# uC_assembly.net
KiCad netlist of a schematic drawn in Altium Designer
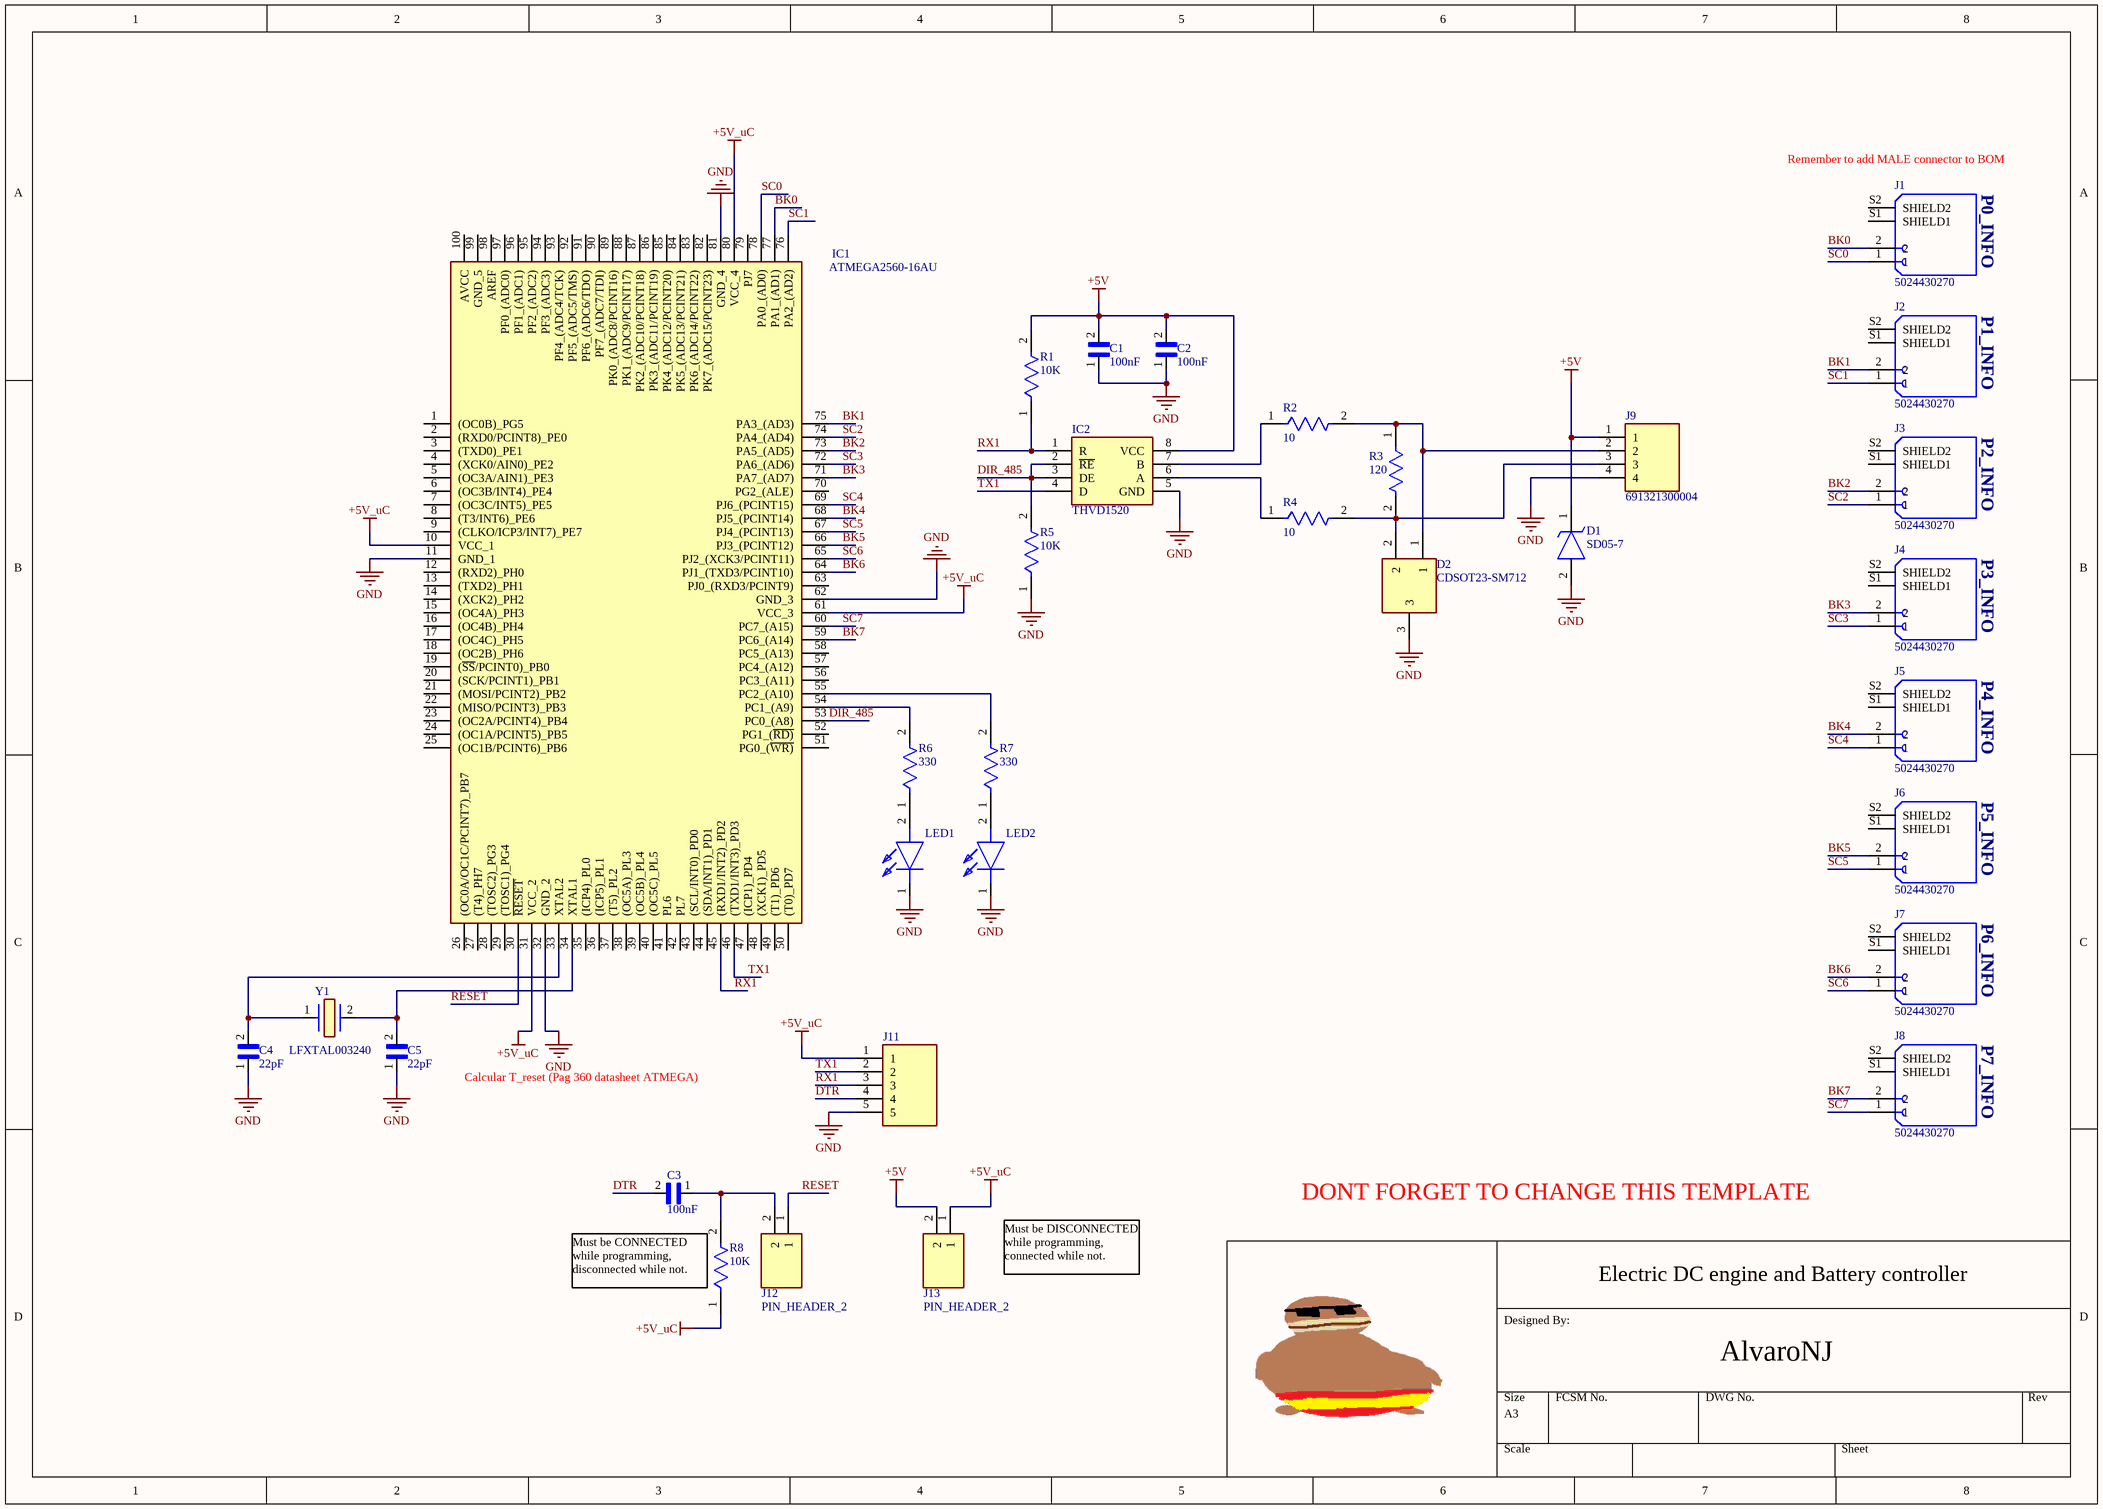
[diagram p0: uC_assembly.SchDoc]

(export (version "E")
  (design (tool "Eeschema 10.0.6"))
  (components
    (comp (ref "C1")
      (value "100nF")
      (footprint "0603C")
      (description "Cap Ceramic 22pF")
      (fields
        (field (name "MANUFACTURER") "Kyocera")
        (field (name "MANUFACTURER PART NUMBER") "KGM15BR71E104KT")
      )
      (libsource (lib "") (part "Ceramic_Capacitor_1"))
    )
    (comp (ref "C2")
      (value "100nF")
      (footprint "0603C")
      (description "Cap Ceramic 22pF")
      (fields
        (field (name "MANUFACTURER") "Kyocera")
        (field (name "MANUFACTURER PART NUMBER") "KGM15BR71E104KT")
      )
      (libsource (lib "") (part "Ceramic_Capacitor_1"))
    )
    (comp (ref "C3")
      (value "100nF")
      (footprint "0603C")
      (description "Cap Ceramic 22pF")
      (fields
        (field (name "MANUFACTURER") "Kyocera")
        (field (name "MANUFACTURER PART NUMBER") "KGM15BR71E104KT")
      )
      (libsource (lib "Schlib1") (part "Ceramic_Capacitor"))
    )
    (comp (ref "C4")
      (value "22pF")
      (footprint "0603C")
      (description "Cap Ceramic 22pF")
      (fields
        (field (name "MANUFACTURER") "Kyocera")
        (field (name "MANUFACTURER PART NUMBER") "KGM15ACG1C220KT")
      )
      (libsource (lib "") (part "Ceramic_Capacitor_1"))
    )
    (comp (ref "C5")
      (value "22pF")
      (footprint "0603C")
      (description "Cap Ceramic 22pF")
      (fields
        (field (name "MANUFACTURER") "Kyocera")
        (field (name "MANUFACTURER PART NUMBER") "KGM15ACG1C220KT")
      )
      (libsource (lib "") (part "Ceramic_Capacitor_1"))
    )
    (comp (ref "D1")
      (value "SD05-7")
      (footprint "PcbLib1:SOD2513X120N")
      (description "TVS Diode (Uni-directional)")
      (fields (field (name "MOUSER PART NUMBER") "621-SD05-7"))
      (libsource (lib "*") (part "SD05-7"))
    )
    (comp (ref "D2")
      (value "CDSOT23-SM712")
      (footprint "PcbLib1:SOT95P230X117-3N")
      (description "Diode")
      (fields (field (name "MOUSER PART NUMBER") "652-CDSOT23-SM712"))
      (libsource (lib "*") (part "CDSOT23-SM712"))
    )
    (comp (ref "IC1")
      (value "ATMEGA2560-16AU")
      (footprint "PcbLib1:QFP50P1600X1600X120-100N")
      (description "Integrated Circuit")
      (fields (field (name "MOUSER PART NUMBER") "556-ATMEGA2560-16AU"))
      (libsource (lib "Schlib1") (part "ATMEGA2560-16AU"))
    )
    (comp (ref "IC2")
      (value "THVD1520")
      (footprint "PcbLib1:SOIC127P600X175-8N")
      (description "Integrated Circuit")
      (libsource (lib "*") (part "THVD1520"))
    )
    (comp (ref "J1")
      (value "5024430270")
      (footprint "MOLEX_5024430270")
      (libsource (lib "Schlib1") (part "5024430270"))
    )
    (comp (ref "J2")
      (value "5024430270")
      (footprint "MOLEX_5024430270")
      (libsource (lib "Schlib1") (part "5024430270"))
    )
    (comp (ref "J3")
      (value "5024430270")
      (footprint "MOLEX_5024430270")
      (libsource (lib "Schlib1") (part "5024430270"))
    )
    (comp (ref "J4")
      (value "5024430270")
      (footprint "MOLEX_5024430270")
      (libsource (lib "Schlib1") (part "5024430270"))
    )
    (comp (ref "J5")
      (value "5024430270")
      (footprint "MOLEX_5024430270")
      (libsource (lib "Schlib1") (part "5024430270"))
    )
    (comp (ref "J6")
      (value "5024430270")
      (footprint "MOLEX_5024430270")
      (libsource (lib "Schlib1") (part "5024430270"))
    )
    (comp (ref "J7")
      (value "5024430270")
      (footprint "MOLEX_5024430270")
      (libsource (lib "Schlib1") (part "5024430270"))
    )
    (comp (ref "J8")
      (value "5024430270")
      (footprint "MOLEX_5024430270")
      (libsource (lib "Schlib1") (part "5024430270"))
    )
    (comp (ref "J9")
      (value "691321300004")
      (footprint "PcbLib1:SHDR4W80P0X381_1X4_1643X720X920P")
      (description "Connector")
      (fields (field (name "MOUSER PART NUMBER") "710-691321300004"))
      (libsource (lib "*") (part "691321300004"))
    )
    (comp (ref "J11")
      (value "MOLEX,_C-GRID_III,_90120,_8_WAY,_1_ROW,_STRAIGHT_PIN_HEADER")
      (footprint "HDRV8W65P0X254_1X8_2010X249X945P - duplicate")
      (description "Connector")
      (fields (field (name "MANUFACTURER_PART_NUMBER") "MOLEX"))
      (libsource (lib "Schlib1") (part "MOLEX,_C-GRID_III,_90120,_8_WAY,_1_ROW,_STRAIGHT_PIN_HEADER"))
    )
    (comp (ref "J12")
      (value "PIN_HEADER_2")
      (footprint "PINHEADER2")
      (description "Connector")
      (fields (field (name "MANUFACTURER_PART_NUMBER") "MOLEX"))
      (libsource (lib "Schlib1") (part "PIN_HEADER_2"))
    )
    (comp (ref "J13")
      (value "PIN_HEADER_2")
      (footprint "PINHEADER2")
      (description "Connector")
      (fields (field (name "MANUFACTURER_PART_NUMBER") "MOLEX"))
      (libsource (lib "Schlib1") (part "PIN_HEADER_2"))
    )
    (comp (ref "LED1")
      (value "LTST-C191KFKT")
      (footprint "PcbLib1:LEDC1608X55N")
      (description "LED")
      (fields (field (name "MANUFACTURER") "Lite-On"))
      (libsource (lib "*") (part "LTST-C191KFKT"))
    )
    (comp (ref "LED2")
      (value "LTST-C191KFKT")
      (footprint "PcbLib1:LEDC1608X55N")
      (description "LED")
      (fields
        (field (name "MANUFACTURER") "Lite-On")
        (field (name "MANUFACTURER PART NUMBER") "LTST-C191KGKT")
      )
      (libsource (lib "*") (part "LTST-C191KFKT"))
    )
    (comp (ref "R1")
      (value "10K")
      (footprint "0603R")
      (fields
        (field (name "MANUFACTURER") "Yageo")
        (field (name "MANUFACTURER PART NUMBER") "RC0603FR-1010KL")
      )
      (libsource (lib "Schlib1") (part "Resistor"))
    )
    (comp (ref "R2")
      (value "10")
      (footprint "0603R")
      (fields
        (field (name "MANUFACTURER") "Yageo")
        (field (name "MANUFACTURER PART NUMBER") "RC0603FR-0710RL")
      )
      (libsource (lib "Schlib1") (part "Resistor"))
    )
    (comp (ref "R3")
      (value "120")
      (footprint "1206R")
      (fields
        (field (name "MANUFACTURER") "Yageo")
        (field (name "MANUFACTURER PART NUMBER") "RC1206FR-07120RL")
      )
      (libsource (lib "Schlib1") (part "Resistor"))
    )
    (comp (ref "R4")
      (value "10")
      (footprint "0603R")
      (fields
        (field (name "MANUFACTURER") "Yageo")
        (field (name "MANUFACTURER PART NUMBER") "RC0603FR-0710RL")
      )
      (libsource (lib "Schlib1") (part "Resistor"))
    )
    (comp (ref "R5")
      (value "10K")
      (footprint "0603R")
      (fields
        (field (name "MANUFACTURER") "Yageo")
        (field (name "MANUFACTURER PART NUMBER") "RC0603FR-1010KL")
      )
      (libsource (lib "Schlib1") (part "Resistor"))
    )
    (comp (ref "R6")
      (value "330")
      (footprint "0603R")
      (fields
        (field (name "MANUFACTURER") "Yageo")
        (field (name "MANUFACTURER PART NUMBER") "RC0603FR-10330RL")
      )
      (libsource (lib "Schlib1") (part "Resistor"))
    )
    (comp (ref "R7")
      (value "330")
      (footprint "0603R")
      (fields
        (field (name "MANUFACTURER") "Yageo")
        (field (name "MANUFACTURER PART NUMBER") "RC0603FR-10330RL")
      )
      (libsource (lib "Schlib1") (part "Resistor"))
    )
    (comp (ref "R8")
      (value "10K")
      (footprint "0603R")
      (fields
        (field (name "MANUFACTURER") "Yageo")
        (field (name "MANUFACTURER PART NUMBER") "RC0603FR-1010KL")
      )
      (libsource (lib "Schlib1") (part "Resistor"))
    )
    (comp (ref "Y1")
      (value "LFXTAL003240")
      (footprint "IQD-HC-49-4H")
      (description "Crystal or Oscillator")
      (libsource (lib "Schlib1") (part "LFXTAL003240"))
    )
  )
  (nets
    (net (code "1") (name "+5V") (class "Default")
      (node (ref "C1") (pin "2") (pinfunction "2_2") (pintype "passive"))
      (node (ref "C2") (pin "2") (pinfunction "2_2") (pintype "passive"))
      (node (ref "D1") (pin "1") (pinfunction "K_1") (pintype "passive"))
      (node (ref "IC2") (pin "8") (pinfunction "VCC_8") (pintype "passive"))
      (node (ref "J13") (pin "2") (pinfunction "2_2") (pintype "passive"))
      (node (ref "J9") (pin "1") (pinfunction "1_1") (pintype "passive"))
      (node (ref "R1") (pin "2") (pinfunction "2_2") (pintype "passive"))
    )
    (net (code "2") (name "+5V_uC") (class "Default")
      (node (ref "IC1") (pin "10") (pinfunction "VCC_1_10") (pintype "passive"))
      (node (ref "IC1") (pin "31") (pinfunction "VCC_2_31") (pintype "passive"))
      (node (ref "IC1") (pin "61") (pinfunction "VCC_3_61") (pintype "passive"))
      (node (ref "IC1") (pin "80") (pinfunction "VCC_4_80") (pintype "passive"))
      (node (ref "J11") (pin "1") (pinfunction "1_1") (pintype "passive"))
      (node (ref "J13") (pin "1") (pinfunction "1_1") (pintype "passive"))
      (node (ref "R8") (pin "1") (pinfunction "1_1") (pintype "passive"))
    )
    (net (code "3") (name "/BK0") (class "Default")
      (node (ref "IC1") (pin "77") (pinfunction "PA1_(AD1)_77") (pintype "passive"))
      (node (ref "J1") (pin "2") (pinfunction "2_2") (pintype "passive"))
    )
    (net (code "4") (name "/BK1") (class "Default")
      (node (ref "IC1") (pin "75") (pinfunction "PA3_(AD3)_75") (pintype "passive"))
      (node (ref "J2") (pin "2") (pinfunction "2_2") (pintype "passive"))
    )
    (net (code "5") (name "/BK2") (class "Default")
      (node (ref "IC1") (pin "73") (pinfunction "PA5_(AD5)_73") (pintype "passive"))
      (node (ref "J3") (pin "2") (pinfunction "2_2") (pintype "passive"))
    )
    (net (code "6") (name "/BK3") (class "Default")
      (node (ref "IC1") (pin "71") (pinfunction "PA7_(AD7)_71") (pintype "passive"))
      (node (ref "J4") (pin "2") (pinfunction "2_2") (pintype "passive"))
    )
    (net (code "7") (name "/BK4") (class "Default")
      (node (ref "IC1") (pin "68") (pinfunction "PJ5_(PCINT14)_68") (pintype "passive"))
      (node (ref "J5") (pin "2") (pinfunction "2_2") (pintype "passive"))
    )
    (net (code "8") (name "/BK5") (class "Default")
      (node (ref "IC1") (pin "66") (pinfunction "PJ3_(PCINT12)_66") (pintype "passive"))
      (node (ref "J6") (pin "2") (pinfunction "2_2") (pintype "passive"))
    )
    (net (code "9") (name "/BK6") (class "Default")
      (node (ref "IC1") (pin "64") (pinfunction "PJ1_(TXD3/PCINT10)_64") (pintype "passive"))
      (node (ref "J7") (pin "2") (pinfunction "2_2") (pintype "passive"))
    )
    (net (code "10") (name "/BK7") (class "Default")
      (node (ref "IC1") (pin "59") (pinfunction "PC6_(A14)_59") (pintype "passive"))
      (node (ref "J8") (pin "2") (pinfunction "2_2") (pintype "passive"))
    )
    (net (code "11") (name "/DIR_485") (class "Default")
      (node (ref "IC1") (pin "53") (pinfunction "PC0_(A8)_53") (pintype "passive"))
      (node (ref "IC2") (pin "2") (pinfunction "~{RE}_2") (pintype "passive"))
      (node (ref "IC2") (pin "3") (pinfunction "DE_3") (pintype "passive"))
      (node (ref "R5") (pin "2") (pinfunction "2_2") (pintype "passive"))
    )
    (net (code "12") (name "/DTR") (class "Default")
      (node (ref "C3") (pin "2") (pinfunction "2_2") (pintype "passive"))
      (node (ref "J11") (pin "4") (pinfunction "4_4") (pintype "passive"))
    )
    (net (code "13") (name "/RESET") (class "Default")
      (node (ref "IC1") (pin "30") (pinfunction "~{RESET}_30") (pintype "passive"))
      (node (ref "J12") (pin "1") (pinfunction "1_1") (pintype "passive"))
    )
    (net (code "14") (name "/RX1") (class "Default")
      (node (ref "IC1") (pin "45") (pinfunction "(RXD1/INT2)_PD2_45") (pintype "passive"))
      (node (ref "IC2") (pin "1") (pinfunction "R_1") (pintype "passive"))
      (node (ref "J11") (pin "3") (pinfunction "3_3") (pintype "passive"))
      (node (ref "R1") (pin "1") (pinfunction "1_1") (pintype "passive"))
    )
    (net (code "15") (name "/SC0") (class "Default")
      (node (ref "IC1") (pin "78") (pinfunction "PA0_(AD0)_78") (pintype "passive"))
      (node (ref "J1") (pin "1") (pinfunction "1_1") (pintype "passive"))
    )
    (net (code "16") (name "/SC1") (class "Default")
      (node (ref "IC1") (pin "76") (pinfunction "PA2_(AD2)_76") (pintype "passive"))
      (node (ref "J2") (pin "1") (pinfunction "1_1") (pintype "passive"))
    )
    (net (code "17") (name "/SC2") (class "Default")
      (node (ref "IC1") (pin "74") (pinfunction "PA4_(AD4)_74") (pintype "passive"))
      (node (ref "J3") (pin "1") (pinfunction "1_1") (pintype "passive"))
    )
    (net (code "18") (name "/SC3") (class "Default")
      (node (ref "IC1") (pin "72") (pinfunction "PA6_(AD6)_72") (pintype "passive"))
      (node (ref "J4") (pin "1") (pinfunction "1_1") (pintype "passive"))
    )
    (net (code "19") (name "/SC4") (class "Default")
      (node (ref "IC1") (pin "69") (pinfunction "PJ6_(PCINT15)_69") (pintype "passive"))
      (node (ref "J5") (pin "1") (pinfunction "1_1") (pintype "passive"))
    )
    (net (code "20") (name "/SC5") (class "Default")
      (node (ref "IC1") (pin "67") (pinfunction "PJ4_(PCINT13)_67") (pintype "passive"))
      (node (ref "J6") (pin "1") (pinfunction "1_1") (pintype "passive"))
    )
    (net (code "21") (name "/SC6") (class "Default")
      (node (ref "IC1") (pin "65") (pinfunction "PJ2_(XCK3/PCINT11)_65") (pintype "passive"))
      (node (ref "J7") (pin "1") (pinfunction "1_1") (pintype "passive"))
    )
    (net (code "22") (name "/SC7") (class "Default")
      (node (ref "IC1") (pin "60") (pinfunction "PC7_(A15)_60") (pintype "passive"))
      (node (ref "J8") (pin "1") (pinfunction "1_1") (pintype "passive"))
    )
    (net (code "23") (name "/TX1") (class "Default")
      (node (ref "IC1") (pin "46") (pinfunction "(TXD1/INT3)_PD3_46") (pintype "passive"))
      (node (ref "IC2") (pin "4") (pinfunction "D_4") (pintype "passive"))
      (node (ref "J11") (pin "2") (pinfunction "2_2") (pintype "passive"))
    )
    (net (code "24") (name "GND") (class "Default")
      (node (ref "C1") (pin "1") (pinfunction "1_1") (pintype "passive"))
      (node (ref "C2") (pin "1") (pinfunction "1_1") (pintype "passive"))
      (node (ref "C4") (pin "1") (pinfunction "1_1") (pintype "passive"))
      (node (ref "C5") (pin "1") (pinfunction "1_1") (pintype "passive"))
      (node (ref "D1") (pin "2") (pinfunction "A_2") (pintype "passive"))
      (node (ref "D2") (pin "3") (pinfunction "3_3") (pintype "passive"))
      (node (ref "IC1") (pin "11") (pinfunction "GND_1_11") (pintype "passive"))
      (node (ref "IC1") (pin "32") (pinfunction "GND_2_32") (pintype "passive"))
      (node (ref "IC1") (pin "62") (pinfunction "GND_3_62") (pintype "passive"))
      (node (ref "IC1") (pin "81") (pinfunction "GND_4_81") (pintype "passive"))
      (node (ref "IC2") (pin "5") (pinfunction "GND_5") (pintype "passive"))
      (node (ref "J11") (pin "5") (pinfunction "5_5") (pintype "passive"))
      (node (ref "J9") (pin "4") (pinfunction "4_4") (pintype "passive"))
      (node (ref "LED1") (pin "1") (pinfunction "K_1") (pintype "passive"))
      (node (ref "LED2") (pin "1") (pinfunction "K_1") (pintype "passive"))
      (node (ref "R5") (pin "1") (pinfunction "1_1") (pintype "passive"))
    )
    (net (code "25") (name "Net-(C3-Pad1)") (class "Default")
      (node (ref "C3") (pin "1") (pinfunction "1_1") (pintype "passive"))
      (node (ref "J12") (pin "2") (pinfunction "2_2") (pintype "passive"))
      (node (ref "R8") (pin "2") (pinfunction "2_2") (pintype "passive"))
    )
    (net (code "26") (name "Net-(D2-Pad1)") (class "Default")
      (node (ref "D2") (pin "1") (pinfunction "1_1") (pintype "passive"))
      (node (ref "J9") (pin "2") (pinfunction "2_2") (pintype "passive"))
      (node (ref "R2") (pin "2") (pinfunction "2_2") (pintype "passive"))
      (node (ref "R3") (pin "1") (pinfunction "1_1") (pintype "passive"))
    )
    (net (code "27") (name "Net-(D2-Pad2)") (class "Default")
      (node (ref "D2") (pin "2") (pinfunction "2_2") (pintype "passive"))
      (node (ref "J9") (pin "3") (pinfunction "3_3") (pintype "passive"))
      (node (ref "R3") (pin "2") (pinfunction "2_2") (pintype "passive"))
      (node (ref "R4") (pin "2") (pinfunction "2_2") (pintype "passive"))
    )
    (net (code "28") (name "Net-(IC1-PC1_(A9))") (class "Default")
      (node (ref "IC1") (pin "54") (pinfunction "PC1_(A9)_54") (pintype "passive"))
      (node (ref "R6") (pin "2") (pinfunction "2_2") (pintype "passive"))
    )
    (net (code "29") (name "Net-(IC1-PC2_(A10))") (class "Default")
      (node (ref "IC1") (pin "55") (pinfunction "PC2_(A10)_55") (pintype "passive"))
      (node (ref "R7") (pin "2") (pinfunction "2_2") (pintype "passive"))
    )
    (net (code "30") (name "Net-(IC1-XTAL1)") (class "Default")
      (node (ref "C5") (pin "2") (pinfunction "2_2") (pintype "passive"))
      (node (ref "IC1") (pin "34") (pinfunction "XTAL1_34") (pintype "passive"))
      (node (ref "Y1") (pin "2") (pinfunction "2_2") (pintype "passive"))
    )
    (net (code "31") (name "Net-(IC1-XTAL2)") (class "Default")
      (node (ref "C4") (pin "2") (pinfunction "2_2") (pintype "passive"))
      (node (ref "IC1") (pin "33") (pinfunction "XTAL2_33") (pintype "passive"))
      (node (ref "Y1") (pin "1") (pinfunction "1_1") (pintype "passive"))
    )
    (net (code "32") (name "Net-(IC2-A)") (class "Default")
      (node (ref "IC2") (pin "6") (pinfunction "A_6") (pintype "passive"))
      (node (ref "R4") (pin "1") (pinfunction "1_1") (pintype "passive"))
    )
    (net (code "33") (name "Net-(IC2-B)") (class "Default")
      (node (ref "IC2") (pin "7") (pinfunction "B_7") (pintype "passive"))
      (node (ref "R2") (pin "1") (pinfunction "1_1") (pintype "passive"))
    )
    (net (code "34") (name "Net-(LED1-A)") (class "Default")
      (node (ref "LED1") (pin "2") (pinfunction "A_2") (pintype "passive"))
      (node (ref "R6") (pin "1") (pinfunction "1_1") (pintype "passive"))
    )
    (net (code "35") (name "Net-(LED2-A)") (class "Default")
      (node (ref "LED2") (pin "2") (pinfunction "A_2") (pintype "passive"))
      (node (ref "R7") (pin "1") (pinfunction "1_1") (pintype "passive"))
    )
    (net (code "36") (name "unconnected-(IC1-(CLKO{slash}ICP3{slash}INT7)_PE7-Pad9)") (class "Default")
      (node (ref "IC1") (pin "9") (pinfunction "(CLKO/ICP3/INT7)_PE7_9") (pintype "passive"))
    )
    (net (code "37") (name "unconnected-(IC1-(ICP1)_PD4-Pad47)") (class "Default")
      (node (ref "IC1") (pin "47") (pinfunction "(ICP1)_PD4_47") (pintype "passive"))
    )
    (net (code "38") (name "unconnected-(IC1-(ICP4)_PL0-Pad35)") (class "Default")
      (node (ref "IC1") (pin "35") (pinfunction "(ICP4)_PL0_35") (pintype "passive"))
    )
    (net (code "39") (name "unconnected-(IC1-(ICP5)_PL1-Pad36)") (class "Default")
      (node (ref "IC1") (pin "36") (pinfunction "(ICP5)_PL1_36") (pintype "passive"))
    )
    (net (code "40") (name "unconnected-(IC1-(MISO{slash}PCINT3)_PB3-Pad22)") (class "Default")
      (node (ref "IC1") (pin "22") (pinfunction "(MISO/PCINT3)_PB3_22") (pintype "passive"))
    )
    (net (code "41") (name "unconnected-(IC1-(MOSI{slash}PCINT2)_PB2-Pad21)") (class "Default")
      (node (ref "IC1") (pin "21") (pinfunction "(MOSI/PCINT2)_PB2_21") (pintype "passive"))
    )
    (net (code "42") (name "unconnected-(IC1-(OC0A{slash}OC1C{slash}PCINT7)_PB7-Pad26)") (class "Default")
      (node (ref "IC1") (pin "26") (pinfunction "(OC0A/OC1C/PCINT7)_PB7_26") (pintype "passive"))
    )
    (net (code "43") (name "unconnected-(IC1-(OC0B)_PG5-Pad1)") (class "Default")
      (node (ref "IC1") (pin "1") (pinfunction "(OC0B)_PG5_1") (pintype "passive"))
    )
    (net (code "44") (name "unconnected-(IC1-(OC1A{slash}PCINT5)_PB5-Pad24)") (class "Default")
      (node (ref "IC1") (pin "24") (pinfunction "(OC1A/PCINT5)_PB5_24") (pintype "passive"))
    )
    (net (code "45") (name "unconnected-(IC1-(OC1B{slash}PCINT6)_PB6-Pad25)") (class "Default")
      (node (ref "IC1") (pin "25") (pinfunction "(OC1B/PCINT6)_PB6_25") (pintype "passive"))
    )
    (net (code "46") (name "unconnected-(IC1-(OC2A{slash}PCINT4)_PB4-Pad23)") (class "Default")
      (node (ref "IC1") (pin "23") (pinfunction "(OC2A/PCINT4)_PB4_23") (pintype "passive"))
    )
    (net (code "47") (name "unconnected-(IC1-(OC2B)_PH6-Pad18)") (class "Default")
      (node (ref "IC1") (pin "18") (pinfunction "(OC2B)_PH6_18") (pintype "passive"))
    )
    (net (code "48") (name "unconnected-(IC1-(OC3A{slash}AIN1)_PE3-Pad5)") (class "Default")
      (node (ref "IC1") (pin "5") (pinfunction "(OC3A/AIN1)_PE3_5") (pintype "passive"))
    )
    (net (code "49") (name "unconnected-(IC1-(OC3B{slash}INT4)_PE4-Pad6)") (class "Default")
      (node (ref "IC1") (pin "6") (pinfunction "(OC3B/INT4)_PE4_6") (pintype "passive"))
    )
    (net (code "50") (name "unconnected-(IC1-(OC3C{slash}INT5)_PE5-Pad7)") (class "Default")
      (node (ref "IC1") (pin "7") (pinfunction "(OC3C/INT5)_PE5_7") (pintype "passive"))
    )
    (net (code "51") (name "unconnected-(IC1-(OC4A)_PH3-Pad15)") (class "Default")
      (node (ref "IC1") (pin "15") (pinfunction "(OC4A)_PH3_15") (pintype "passive"))
    )
    (net (code "52") (name "unconnected-(IC1-(OC4B)_PH4-Pad16)") (class "Default")
      (node (ref "IC1") (pin "16") (pinfunction "(OC4B)_PH4_16") (pintype "passive"))
    )
    (net (code "53") (name "unconnected-(IC1-(OC4C)_PH5-Pad17)") (class "Default")
      (node (ref "IC1") (pin "17") (pinfunction "(OC4C)_PH5_17") (pintype "passive"))
    )
    (net (code "54") (name "unconnected-(IC1-(OC5A)_PL3-Pad38)") (class "Default")
      (node (ref "IC1") (pin "38") (pinfunction "(OC5A)_PL3_38") (pintype "passive"))
    )
    (net (code "55") (name "unconnected-(IC1-(OC5B)_PL4-Pad39)") (class "Default")
      (node (ref "IC1") (pin "39") (pinfunction "(OC5B)_PL4_39") (pintype "passive"))
    )
    (net (code "56") (name "unconnected-(IC1-(OC5C)_PL5-Pad40)") (class "Default")
      (node (ref "IC1") (pin "40") (pinfunction "(OC5C)_PL5_40") (pintype "passive"))
    )
    (net (code "57") (name "unconnected-(IC1-(RXD0{slash}PCINT8)_PE0-Pad2)") (class "Default")
      (node (ref "IC1") (pin "2") (pinfunction "(RXD0/PCINT8)_PE0_2") (pintype "passive"))
    )
    (net (code "58") (name "unconnected-(IC1-(RXD2)_PH0-Pad12)") (class "Default")
      (node (ref "IC1") (pin "12") (pinfunction "(RXD2)_PH0_12") (pintype "passive"))
    )
    (net (code "59") (name "unconnected-(IC1-(SCK{slash}PCINT1)_PB1-Pad20)") (class "Default")
      (node (ref "IC1") (pin "20") (pinfunction "(SCK/PCINT1)_PB1_20") (pintype "passive"))
    )
    (net (code "60") (name "unconnected-(IC1-(SCL{slash}INT0)_PD0-Pad43)") (class "Default")
      (node (ref "IC1") (pin "43") (pinfunction "(SCL/INT0)_PD0_43") (pintype "passive"))
    )
    (net (code "61") (name "unconnected-(IC1-(SDA{slash}INT1)_PD1-Pad44)") (class "Default")
      (node (ref "IC1") (pin "44") (pinfunction "(SDA/INT1)_PD1_44") (pintype "passive"))
    )
    (net (code "62") (name "unconnected-(IC1-(T0)_PD7-Pad50)") (class "Default")
      (node (ref "IC1") (pin "50") (pinfunction "(T0)_PD7_50") (pintype "passive"))
    )
    (net (code "63") (name "unconnected-(IC1-(T1)_PD6-Pad49)") (class "Default")
      (node (ref "IC1") (pin "49") (pinfunction "(T1)_PD6_49") (pintype "passive"))
    )
    (net (code "64") (name "unconnected-(IC1-(T3{slash}INT6)_PE6-Pad8)") (class "Default")
      (node (ref "IC1") (pin "8") (pinfunction "(T3/INT6)_PE6_8") (pintype "passive"))
    )
    (net (code "65") (name "unconnected-(IC1-(T4)_PH7-Pad27)") (class "Default")
      (node (ref "IC1") (pin "27") (pinfunction "(T4)_PH7_27") (pintype "passive"))
    )
    (net (code "66") (name "unconnected-(IC1-(T5)_PL2-Pad37)") (class "Default")
      (node (ref "IC1") (pin "37") (pinfunction "(T5)_PL2_37") (pintype "passive"))
    )
    (net (code "67") (name "unconnected-(IC1-(TOSC1)_PG4-Pad29)") (class "Default")
      (node (ref "IC1") (pin "29") (pinfunction "(TOSC1)_PG4_29") (pintype "passive"))
    )
    (net (code "68") (name "unconnected-(IC1-(TOSC2)_PG3-Pad28)") (class "Default")
      (node (ref "IC1") (pin "28") (pinfunction "(TOSC2)_PG3_28") (pintype "passive"))
    )
    (net (code "69") (name "unconnected-(IC1-(TXD0)_PE1-Pad3)") (class "Default")
      (node (ref "IC1") (pin "3") (pinfunction "(TXD0)_PE1_3") (pintype "passive"))
    )
    (net (code "70") (name "unconnected-(IC1-(TXD2)_PH1-Pad13)") (class "Default")
      (node (ref "IC1") (pin "13") (pinfunction "(TXD2)_PH1_13") (pintype "passive"))
    )
    (net (code "71") (name "unconnected-(IC1-(XCK0{slash}AIN0)_PE2-Pad4)") (class "Default")
      (node (ref "IC1") (pin "4") (pinfunction "(XCK0/AIN0)_PE2_4") (pintype "passive"))
    )
    (net (code "72") (name "unconnected-(IC1-(XCK1)_PD5-Pad48)") (class "Default")
      (node (ref "IC1") (pin "48") (pinfunction "(XCK1)_PD5_48") (pintype "passive"))
    )
    (net (code "73") (name "unconnected-(IC1-(XCK2)_PH2-Pad14)") (class "Default")
      (node (ref "IC1") (pin "14") (pinfunction "(XCK2)_PH2_14") (pintype "passive"))
    )
    (net (code "74") (name "unconnected-(IC1-(~{SS}{slash}PCINT0)_PB0-Pad19)") (class "Default")
      (node (ref "IC1") (pin "19") (pinfunction "(~{SS}/PCINT0)_PB0_19") (pintype "passive"))
    )
    (net (code "75") (name "unconnected-(IC1-AREF-Pad98)") (class "Default")
      (node (ref "IC1") (pin "98") (pinfunction "AREF_98") (pintype "passive"))
    )
    (net (code "76") (name "unconnected-(IC1-AVCC-Pad100)") (class "Default")
      (node (ref "IC1") (pin "100") (pinfunction "AVCC_100") (pintype "passive"))
    )
    (net (code "77") (name "unconnected-(IC1-GND_5-Pad99)") (class "Default")
      (node (ref "IC1") (pin "99") (pinfunction "GND_5_99") (pintype "passive"))
    )
    (net (code "78") (name "unconnected-(IC1-PC3_(A11)-Pad56)") (class "Default")
      (node (ref "IC1") (pin "56") (pinfunction "PC3_(A11)_56") (pintype "passive"))
    )
    (net (code "79") (name "unconnected-(IC1-PC4_(A12)-Pad57)") (class "Default")
      (node (ref "IC1") (pin "57") (pinfunction "PC4_(A12)_57") (pintype "passive"))
    )
    (net (code "80") (name "unconnected-(IC1-PC5_(A13)-Pad58)") (class "Default")
      (node (ref "IC1") (pin "58") (pinfunction "PC5_(A13)_58") (pintype "passive"))
    )
    (net (code "81") (name "unconnected-(IC1-PF0_(ADC0)-Pad97)") (class "Default")
      (node (ref "IC1") (pin "97") (pinfunction "PF0_(ADC0)_97") (pintype "passive"))
    )
    (net (code "82") (name "unconnected-(IC1-PF1_(ADC1)-Pad96)") (class "Default")
      (node (ref "IC1") (pin "96") (pinfunction "PF1_(ADC1)_96") (pintype "passive"))
    )
    (net (code "83") (name "unconnected-(IC1-PF2_(ADC2)-Pad95)") (class "Default")
      (node (ref "IC1") (pin "95") (pinfunction "PF2_(ADC2)_95") (pintype "passive"))
    )
    (net (code "84") (name "unconnected-(IC1-PF3_(ADC3)-Pad94)") (class "Default")
      (node (ref "IC1") (pin "94") (pinfunction "PF3_(ADC3)_94") (pintype "passive"))
    )
    (net (code "85") (name "unconnected-(IC1-PF4_(ADC4{slash}TCK)-Pad93)") (class "Default")
      (node (ref "IC1") (pin "93") (pinfunction "PF4_(ADC4/TCK)_93") (pintype "passive"))
    )
    (net (code "86") (name "unconnected-(IC1-PF5_(ADC5{slash}TMS)-Pad92)") (class "Default")
      (node (ref "IC1") (pin "92") (pinfunction "PF5_(ADC5/TMS)_92") (pintype "passive"))
    )
    (net (code "87") (name "unconnected-(IC1-PF6_(ADC6{slash}TDO)-Pad91)") (class "Default")
      (node (ref "IC1") (pin "91") (pinfunction "PF6_(ADC6/TDO)_91") (pintype "passive"))
    )
    (net (code "88") (name "unconnected-(IC1-PF7_(ADC7{slash}TDI)-Pad90)") (class "Default")
      (node (ref "IC1") (pin "90") (pinfunction "PF7_(ADC7/TDI)_90") (pintype "passive"))
    )
    (net (code "89") (name "unconnected-(IC1-PG0_(~{WR)}-Pad51)") (class "Default")
      (node (ref "IC1") (pin "51") (pinfunction "PG0_(~{WR)}_51") (pintype "passive"))
    )
    (net (code "90") (name "unconnected-(IC1-PG1_(~{RD)}-Pad52)") (class "Default")
      (node (ref "IC1") (pin "52") (pinfunction "PG1_(~{RD)}_52") (pintype "passive"))
    )
    (net (code "91") (name "unconnected-(IC1-PG2_(ALE)-Pad70)") (class "Default")
      (node (ref "IC1") (pin "70") (pinfunction "PG2_(ALE)_70") (pintype "passive"))
    )
    (net (code "92") (name "unconnected-(IC1-PJ0_(RXD3{slash}PCINT9)-Pad63)") (class "Default")
      (node (ref "IC1") (pin "63") (pinfunction "PJ0_(RXD3/PCINT9)_63") (pintype "passive"))
    )
    (net (code "93") (name "unconnected-(IC1-PJ7-Pad79)") (class "Default")
      (node (ref "IC1") (pin "79") (pinfunction "PJ7_79") (pintype "passive"))
    )
    (net (code "94") (name "unconnected-(IC1-PK0_(ADC8{slash}PCINT16)-Pad89)") (class "Default")
      (node (ref "IC1") (pin "89") (pinfunction "PK0_(ADC8/PCINT16)_89") (pintype "passive"))
    )
    (net (code "95") (name "unconnected-(IC1-PK1_(ADC9{slash}PCINT17)-Pad88)") (class "Default")
      (node (ref "IC1") (pin "88") (pinfunction "PK1_(ADC9/PCINT17)_88") (pintype "passive"))
    )
    (net (code "96") (name "unconnected-(IC1-PK2_(ADC10{slash}PCINT18)-Pad87)") (class "Default")
      (node (ref "IC1") (pin "87") (pinfunction "PK2_(ADC10/PCINT18)_87") (pintype "passive"))
    )
    (net (code "97") (name "unconnected-(IC1-PK3_(ADC11{slash}PCINT19)-Pad86)") (class "Default")
      (node (ref "IC1") (pin "86") (pinfunction "PK3_(ADC11/PCINT19)_86") (pintype "passive"))
    )
    (net (code "98") (name "unconnected-(IC1-PK4_(ADC12{slash}PCINT20)-Pad85)") (class "Default")
      (node (ref "IC1") (pin "85") (pinfunction "PK4_(ADC12/PCINT20)_85") (pintype "passive"))
    )
    (net (code "99") (name "unconnected-(IC1-PK5_(ADC13{slash}PCINT21)-Pad84)") (class "Default")
      (node (ref "IC1") (pin "84") (pinfunction "PK5_(ADC13/PCINT21)_84") (pintype "passive"))
    )
    (net (code "100") (name "unconnected-(IC1-PK6_(ADC14{slash}PCINT22)-Pad83)") (class "Default")
      (node (ref "IC1") (pin "83") (pinfunction "PK6_(ADC14/PCINT22)_83") (pintype "passive"))
    )
    (net (code "101") (name "unconnected-(IC1-PK7_(ADC15{slash}PCINT23)-Pad82)") (class "Default")
      (node (ref "IC1") (pin "82") (pinfunction "PK7_(ADC15/PCINT23)_82") (pintype "passive"))
    )
    (net (code "102") (name "unconnected-(IC1-PL6-Pad41)") (class "Default")
      (node (ref "IC1") (pin "41") (pinfunction "PL6_41") (pintype "passive"))
    )
    (net (code "103") (name "unconnected-(IC1-PL7-Pad42)") (class "Default")
      (node (ref "IC1") (pin "42") (pinfunction "PL7_42") (pintype "passive"))
    )
    (net (code "104") (name "unconnected-(J1-SHIELD1-PadS1)") (class "Default")
      (node (ref "J1") (pin "S1") (pinfunction "SHIELD1_S1") (pintype "passive"))
    )
    (net (code "105") (name "unconnected-(J1-SHIELD2-PadS2)") (class "Default")
      (node (ref "J1") (pin "S2") (pinfunction "SHIELD2_S2") (pintype "passive"))
    )
    (net (code "106") (name "unconnected-(J2-SHIELD1-PadS1)") (class "Default")
      (node (ref "J2") (pin "S1") (pinfunction "SHIELD1_S1") (pintype "passive"))
    )
    (net (code "107") (name "unconnected-(J2-SHIELD2-PadS2)") (class "Default")
      (node (ref "J2") (pin "S2") (pinfunction "SHIELD2_S2") (pintype "passive"))
    )
    (net (code "108") (name "unconnected-(J3-SHIELD1-PadS1)") (class "Default")
      (node (ref "J3") (pin "S1") (pinfunction "SHIELD1_S1") (pintype "passive"))
    )
    (net (code "109") (name "unconnected-(J3-SHIELD2-PadS2)") (class "Default")
      (node (ref "J3") (pin "S2") (pinfunction "SHIELD2_S2") (pintype "passive"))
    )
    (net (code "110") (name "unconnected-(J4-SHIELD1-PadS1)") (class "Default")
      (node (ref "J4") (pin "S1") (pinfunction "SHIELD1_S1") (pintype "passive"))
    )
    (net (code "111") (name "unconnected-(J4-SHIELD2-PadS2)") (class "Default")
      (node (ref "J4") (pin "S2") (pinfunction "SHIELD2_S2") (pintype "passive"))
    )
    (net (code "112") (name "unconnected-(J5-SHIELD1-PadS1)") (class "Default")
      (node (ref "J5") (pin "S1") (pinfunction "SHIELD1_S1") (pintype "passive"))
    )
    (net (code "113") (name "unconnected-(J5-SHIELD2-PadS2)") (class "Default")
      (node (ref "J5") (pin "S2") (pinfunction "SHIELD2_S2") (pintype "passive"))
    )
    (net (code "114") (name "unconnected-(J6-SHIELD1-PadS1)") (class "Default")
      (node (ref "J6") (pin "S1") (pinfunction "SHIELD1_S1") (pintype "passive"))
    )
    (net (code "115") (name "unconnected-(J6-SHIELD2-PadS2)") (class "Default")
      (node (ref "J6") (pin "S2") (pinfunction "SHIELD2_S2") (pintype "passive"))
    )
    (net (code "116") (name "unconnected-(J7-SHIELD1-PadS1)") (class "Default")
      (node (ref "J7") (pin "S1") (pinfunction "SHIELD1_S1") (pintype "passive"))
    )
    (net (code "117") (name "unconnected-(J7-SHIELD2-PadS2)") (class "Default")
      (node (ref "J7") (pin "S2") (pinfunction "SHIELD2_S2") (pintype "passive"))
    )
    (net (code "118") (name "unconnected-(J8-SHIELD1-PadS1)") (class "Default")
      (node (ref "J8") (pin "S1") (pinfunction "SHIELD1_S1") (pintype "passive"))
    )
    (net (code "119") (name "unconnected-(J8-SHIELD2-PadS2)") (class "Default")
      (node (ref "J8") (pin "S2") (pinfunction "SHIELD2_S2") (pintype "passive"))
    )
  )
)
